# STM32F405GTV6.net
KiCad netlist of a schematic drawn in Altium Designer
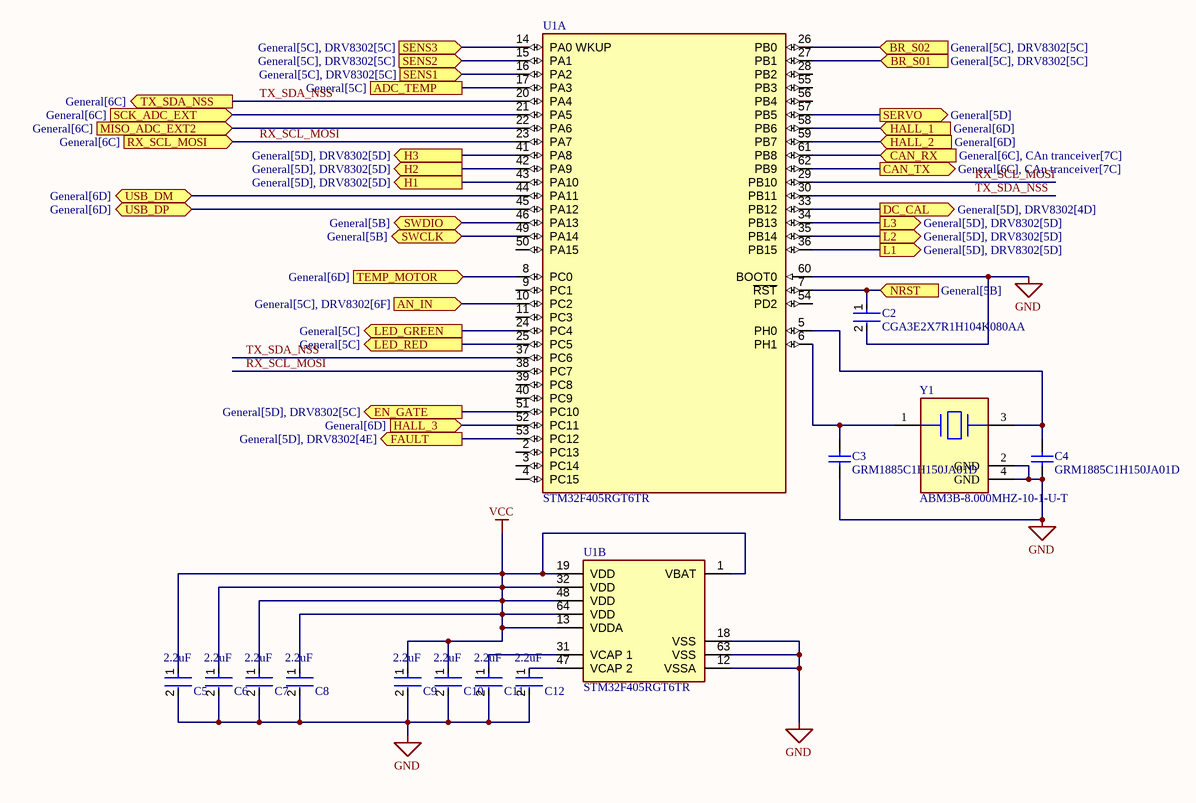
[diagram p0: STM32F405GTV6.SchDoc]

(export (version "E")
  (design (tool "Eeschema 10.0.6"))
  (components
    (comp (ref "C2")
      (value "CGA3E2X7R1H104K080AA")
      (footprint "FP-CGA3E-0_3-0_1-IPC_A")
      (description "Cap Ceramic 100nF 50V X7R 10% Pad SMD 0603 +125°C Automotive T/R")
      (fields (field (name "TOLERANCE") "10%") (field (name "VOLTAGE") "50V"))
      (libsource (lib "Altium Content Vault") (part "b4654b650e69147ec39a6b967a45e02"))
    )
    (comp (ref "C3")
      (value "GRM1885C1H150JA01D")
      (footprint "CAPC1608X90X35ML10T15")
      (fields (field (name "MANUFACTURER") "Murata"))
      (libsource (lib "Altium Content Vault") (part "CAP"))
    )
    (comp (ref "C4")
      (value "GRM1885C1H150JA01D")
      (footprint "CAPC1608X90X35ML10T15")
      (fields (field (name "MANUFACTURER") "Murata"))
      (libsource (lib "Altium Content Vault") (part "CAP"))
    )
    (comp (ref "C5")
      (value "GRM188R71A225KE15D")
      (footprint "FP-GRM188-0_1-e0_2_0_5-MFG")
      (description "Chip Multilayer Ceramic Capacitors for General Purpose, 0603, 2.2uF, X7R, 15%, 10%, 10V")
      (fields
        (field (name "VOLTAGE") "10V")
        (field (name "CAPACITANCE") "2.2uF")
        (field (name "TOLERANCE") "10%")
      )
      (libsource (lib "Altium Content Vault") (part "11868f565c42a9108669ba33697ecf6"))
    )
    (comp (ref "C6")
      (value "GRM188R71A225KE15D")
      (footprint "FP-GRM188-0_1-e0_2_0_5-MFG")
      (description "Chip Multilayer Ceramic Capacitors for General Purpose, 0603, 2.2uF, X7R, 15%, 10%, 10V")
      (fields
        (field (name "VOLTAGE") "10V")
        (field (name "CAPACITANCE") "2.2uF")
        (field (name "TOLERANCE") "10%")
      )
      (libsource (lib "Altium Content Vault") (part "11868f565c42a9108669ba33697ecf6"))
    )
    (comp (ref "C7")
      (value "GRM188R71A225KE15D")
      (footprint "FP-GRM188-0_1-e0_2_0_5-MFG")
      (description "Chip Multilayer Ceramic Capacitors for General Purpose, 0603, 2.2uF, X7R, 15%, 10%, 10V")
      (fields
        (field (name "VOLTAGE") "10V")
        (field (name "CAPACITANCE") "2.2uF")
        (field (name "TOLERANCE") "10%")
      )
      (libsource (lib "Altium Content Vault") (part "11868f565c42a9108669ba33697ecf6"))
    )
    (comp (ref "C8")
      (value "GRM188R71A225KE15D")
      (footprint "FP-GRM188-0_1-e0_2_0_5-MFG")
      (description "Chip Multilayer Ceramic Capacitors for General Purpose, 0603, 2.2uF, X7R, 15%, 10%, 10V")
      (fields
        (field (name "VOLTAGE") "10V")
        (field (name "CAPACITANCE") "2.2uF")
        (field (name "TOLERANCE") "10%")
      )
      (libsource (lib "Altium Content Vault") (part "11868f565c42a9108669ba33697ecf6"))
    )
    (comp (ref "C9")
      (value "GRM188R71A225KE15D")
      (footprint "FP-GRM188-0_1-e0_2_0_5-MFG")
      (description "Chip Multilayer Ceramic Capacitors for General Purpose, 0603, 2.2uF, X7R, 15%, 10%, 10V")
      (fields
        (field (name "VOLTAGE") "10V")
        (field (name "CAPACITANCE") "2.2uF")
        (field (name "TOLERANCE") "10%")
      )
      (libsource (lib "Altium Content Vault") (part "11868f565c42a9108669ba33697ecf6"))
    )
    (comp (ref "C10")
      (value "GRM188R71A225KE15D")
      (footprint "FP-GRM188-0_1-e0_2_0_5-MFG")
      (description "Chip Multilayer Ceramic Capacitors for General Purpose, 0603, 2.2uF, X7R, 15%, 10%, 10V")
      (fields
        (field (name "VOLTAGE") "10V")
        (field (name "CAPACITANCE") "2.2uF")
        (field (name "TOLERANCE") "10%")
      )
      (libsource (lib "Altium Content Vault") (part "11868f565c42a9108669ba33697ecf6"))
    )
    (comp (ref "C11")
      (value "GRM188R71A225KE15D")
      (footprint "FP-GRM188-0_1-e0_2_0_5-MFG")
      (description "Chip Multilayer Ceramic Capacitors for General Purpose, 0603, 2.2uF, X7R, 15%, 10%, 10V")
      (fields
        (field (name "VOLTAGE") "10V")
        (field (name "CAPACITANCE") "2.2uF")
        (field (name "TOLERANCE") "10%")
      )
      (libsource (lib "Altium Content Vault") (part "11868f565c42a9108669ba33697ecf6"))
    )
    (comp (ref "C12")
      (value "2u2")
      (footprint "FP-GRM188-0_1-e0_2_0_5-MFG")
      (description "Chip Multilayer Ceramic Capacitors for General Purpose, 0603, 2.2uF, X7R, 15%, 10%, 10V")
      (fields
        (field (name "VOLTAGE") "10V")
        (field (name "CAPACITANCE") "2.2uF")
        (field (name "TOLERANCE") "10%")
      )
      (libsource (lib "Altium Content Vault") (part "11868f565c42a9108669ba33697ecf6"))
    )
    (comp (ref "U1")
      (value "STM32F405RGT6TR")
      (footprint "FP-LQFP64-5W-IPC_C")
      (description "IC MCU 32BIT 1MB FLASH 64LQFP")
      (libsource (lib "Altium Content Vault") (part "179ee1be0515346e2f7079deece093b"))
    )
    (comp (ref "Y1")
      (value "ABM3B-8.000MHZ-10-1-U-T")
      (footprint "FP-ABM3B-MFG")
      (description "Crystal 8MHz ±10ppm 10pF SMD-4 5mm x 3.2mm")
      (libsource (lib "Altium Content Vault") (part "48e526d86b7f2615d98721063c72f49"))
    )
  )
  (nets
    (net (code "1") (name "/ADC_TEMP") (class "Default")
      (node (ref "U1") (pin "17") (pinfunction "PA3_17") (pintype "bidirectional"))
    )
    (net (code "2") (name "/AN_IN") (class "Default")
      (node (ref "U1") (pin "10") (pinfunction "PC2_10") (pintype "bidirectional"))
    )
    (net (code "3") (name "/BR_S01") (class "Default")
      (node (ref "U1") (pin "27") (pinfunction "PB1_27") (pintype "bidirectional"))
    )
    (net (code "4") (name "/BR_S02") (class "Default")
      (node (ref "U1") (pin "26") (pinfunction "PB0_26") (pintype "bidirectional"))
    )
    (net (code "5") (name "/CAN_RX") (class "Default")
      (node (ref "U1") (pin "61") (pinfunction "PB8_61") (pintype "bidirectional"))
    )
    (net (code "6") (name "/CAN_TX") (class "Default")
      (node (ref "U1") (pin "62") (pinfunction "PB9_62") (pintype "bidirectional"))
    )
    (net (code "7") (name "/DC_CAL") (class "Default")
      (node (ref "U1") (pin "33") (pinfunction "PB12_33") (pintype "bidirectional"))
    )
    (net (code "8") (name "/EN_GATE") (class "Default")
      (node (ref "U1") (pin "51") (pinfunction "PC10_51") (pintype "bidirectional"))
    )
    (net (code "9") (name "/FAULT") (class "Default")
      (node (ref "U1") (pin "53") (pinfunction "PC12_53") (pintype "bidirectional"))
    )
    (net (code "10") (name "/H1") (class "Default")
      (node (ref "U1") (pin "43") (pinfunction "PA10_43") (pintype "bidirectional"))
    )
    (net (code "11") (name "/H2") (class "Default")
      (node (ref "U1") (pin "42") (pinfunction "PA9_42") (pintype "bidirectional"))
    )
    (net (code "12") (name "/H3") (class "Default")
      (node (ref "U1") (pin "41") (pinfunction "PA8_41") (pintype "bidirectional"))
    )
    (net (code "13") (name "/HALL_1") (class "Default")
      (node (ref "U1") (pin "58") (pinfunction "PB6_58") (pintype "bidirectional"))
    )
    (net (code "14") (name "/HALL_2") (class "Default")
      (node (ref "U1") (pin "59") (pinfunction "PB7_59") (pintype "bidirectional"))
    )
    (net (code "15") (name "/HALL_3") (class "Default")
      (node (ref "U1") (pin "52") (pinfunction "PC11_52") (pintype "bidirectional"))
    )
    (net (code "16") (name "/L1") (class "Default")
      (node (ref "U1") (pin "36") (pinfunction "PB15_36") (pintype "bidirectional"))
    )
    (net (code "17") (name "/L2") (class "Default")
      (node (ref "U1") (pin "35") (pinfunction "PB14_35") (pintype "bidirectional"))
    )
    (net (code "18") (name "/L3") (class "Default")
      (node (ref "U1") (pin "34") (pinfunction "PB13_34") (pintype "bidirectional"))
    )
    (net (code "19") (name "/LED_GREEN") (class "Default")
      (node (ref "U1") (pin "24") (pinfunction "PC4_24") (pintype "bidirectional"))
    )
    (net (code "20") (name "/LED_RED") (class "Default")
      (node (ref "U1") (pin "25") (pinfunction "PC5_25") (pintype "bidirectional"))
    )
    (net (code "21") (name "/MISO_ADC_EXT2") (class "Default")
      (node (ref "U1") (pin "22") (pinfunction "PA6_22") (pintype "bidirectional"))
    )
    (net (code "22") (name "/NRST") (class "Default")
      (node (ref "C2") (pin "1") (pinfunction "1_1") (pintype "passive"))
      (node (ref "U1") (pin "7") (pinfunction "~{RST}_7") (pintype "bidirectional"))
    )
    (net (code "23") (name "/RX_SCL_MOSI") (class "Default")
      (node (ref "U1") (pin "23") (pinfunction "PA7_23") (pintype "bidirectional"))
      (node (ref "U1") (pin "29") (pinfunction "PB10_29") (pintype "bidirectional"))
      (node (ref "U1") (pin "38") (pinfunction "PC7_38") (pintype "bidirectional"))
    )
    (net (code "24") (name "/SCK_ADC_EXT") (class "Default")
      (node (ref "U1") (pin "21") (pinfunction "PA5_21") (pintype "bidirectional"))
    )
    (net (code "25") (name "/SENS1") (class "Default")
      (node (ref "U1") (pin "16") (pinfunction "PA2_16") (pintype "bidirectional"))
    )
    (net (code "26") (name "/SENS2") (class "Default")
      (node (ref "U1") (pin "15") (pinfunction "PA1_15") (pintype "bidirectional"))
    )
    (net (code "27") (name "/SENS3") (class "Default")
      (node (ref "U1") (pin "14") (pinfunction "PA0_WKUP_14") (pintype "bidirectional"))
    )
    (net (code "28") (name "/SERVO") (class "Default")
      (node (ref "U1") (pin "57") (pinfunction "PB5_57") (pintype "bidirectional"))
    )
    (net (code "29") (name "/SWCLK") (class "Default")
      (node (ref "U1") (pin "49") (pinfunction "PA14_49") (pintype "bidirectional"))
    )
    (net (code "30") (name "/SWDIO") (class "Default")
      (node (ref "U1") (pin "46") (pinfunction "PA13_46") (pintype "bidirectional"))
    )
    (net (code "31") (name "/TEMP_MOTOR") (class "Default")
      (node (ref "U1") (pin "8") (pinfunction "PC0_8") (pintype "bidirectional"))
    )
    (net (code "32") (name "/TX_SDA_NSS") (class "Default")
      (node (ref "U1") (pin "20") (pinfunction "PA4_20") (pintype "bidirectional"))
      (node (ref "U1") (pin "30") (pinfunction "PB11_30") (pintype "bidirectional"))
      (node (ref "U1") (pin "37") (pinfunction "PC6_37") (pintype "bidirectional"))
    )
    (net (code "33") (name "/USB_DM") (class "Default")
      (node (ref "U1") (pin "44") (pinfunction "PA11_44") (pintype "bidirectional"))
    )
    (net (code "34") (name "/USB_DP") (class "Default")
      (node (ref "U1") (pin "45") (pinfunction "PA12_45") (pintype "bidirectional"))
    )
    (net (code "35") (name "GND") (class "Default")
      (node (ref "C10") (pin "2") (pinfunction "2_2") (pintype "passive"))
      (node (ref "C11") (pin "2") (pinfunction "2_2") (pintype "passive"))
      (node (ref "C12") (pin "2") (pinfunction "2_2") (pintype "passive"))
      (node (ref "C2") (pin "2") (pinfunction "2_2") (pintype "passive"))
      (node (ref "C3") (pin "1") (pinfunction "1_1") (pintype "passive"))
      (node (ref "C4") (pin "1") (pinfunction "1_1") (pintype "passive"))
      (node (ref "C5") (pin "2") (pinfunction "2_2") (pintype "passive"))
      (node (ref "C6") (pin "2") (pinfunction "2_2") (pintype "passive"))
      (node (ref "C7") (pin "2") (pinfunction "2_2") (pintype "passive"))
      (node (ref "C8") (pin "2") (pinfunction "2_2") (pintype "passive"))
      (node (ref "C9") (pin "2") (pinfunction "2_2") (pintype "passive"))
      (node (ref "U1") (pin "12") (pinfunction "VSSA_12") (pintype "power_in"))
      (node (ref "U1") (pin "18") (pinfunction "VSS_18") (pintype "power_in"))
      (node (ref "U1") (pin "60") (pinfunction "BOOT0_60") (pintype "input"))
      (node (ref "U1") (pin "63") (pinfunction "VSS_63") (pintype "power_in"))
      (node (ref "Y1") (pin "2") (pinfunction "GND_2") (pintype "power_in"))
      (node (ref "Y1") (pin "4") (pinfunction "GND_4") (pintype "power_in"))
    )
    (net (code "36") (name "Net-(U1A-PH0)") (class "Default")
      (node (ref "C4") (pin "2") (pinfunction "2_2") (pintype "passive"))
      (node (ref "U1") (pin "5") (pinfunction "PH0_5") (pintype "bidirectional"))
      (node (ref "Y1") (pin "3") (pinfunction "3_3") (pintype "passive"))
    )
    (net (code "37") (name "Net-(U1A-PH1)") (class "Default")
      (node (ref "C3") (pin "2") (pinfunction "2_2") (pintype "passive"))
      (node (ref "U1") (pin "6") (pinfunction "PH1_6") (pintype "bidirectional"))
      (node (ref "Y1") (pin "1") (pinfunction "1_1") (pintype "passive"))
    )
    (net (code "38") (name "Net-(U1B-VCAP_1)") (class "Default")
      (node (ref "C11") (pin "1") (pinfunction "1_1") (pintype "passive"))
      (node (ref "U1") (pin "31") (pinfunction "VCAP_1_31") (pintype "passive"))
    )
    (net (code "39") (name "Net-(U1B-VCAP_2)") (class "Default")
      (node (ref "C12") (pin "1") (pinfunction "1_1") (pintype "passive"))
      (node (ref "U1") (pin "47") (pinfunction "VCAP_2_47") (pintype "passive"))
    )
    (net (code "40") (name "VCC") (class "Default")
      (node (ref "C10") (pin "1") (pinfunction "1_1") (pintype "passive"))
      (node (ref "C5") (pin "1") (pinfunction "1_1") (pintype "passive"))
      (node (ref "C6") (pin "1") (pinfunction "1_1") (pintype "passive"))
      (node (ref "C7") (pin "1") (pinfunction "1_1") (pintype "passive"))
      (node (ref "C8") (pin "1") (pinfunction "1_1") (pintype "passive"))
      (node (ref "C9") (pin "1") (pinfunction "1_1") (pintype "passive"))
      (node (ref "U1") (pin "1") (pinfunction "VBAT_1") (pintype "power_in"))
      (node (ref "U1") (pin "13") (pinfunction "VDDA_13") (pintype "power_in"))
      (node (ref "U1") (pin "19") (pinfunction "VDD_19") (pintype "power_in"))
      (node (ref "U1") (pin "32") (pinfunction "VDD_32") (pintype "power_in"))
      (node (ref "U1") (pin "48") (pinfunction "VDD_48") (pintype "power_in"))
      (node (ref "U1") (pin "64") (pinfunction "VDD_64") (pintype "power_in"))
    )
    (net (code "41") (name "unconnected-(U1A-PA15-Pad50)") (class "Default")
      (node (ref "U1") (pin "50") (pinfunction "PA15_50") (pintype "bidirectional"))
    )
    (net (code "42") (name "unconnected-(U1A-PB2-Pad28)") (class "Default")
      (node (ref "U1") (pin "28") (pinfunction "PB2_28") (pintype "bidirectional"))
    )
    (net (code "43") (name "unconnected-(U1A-PB3-Pad55)") (class "Default")
      (node (ref "U1") (pin "55") (pinfunction "PB3_55") (pintype "bidirectional"))
    )
    (net (code "44") (name "unconnected-(U1A-PB4-Pad56)") (class "Default")
      (node (ref "U1") (pin "56") (pinfunction "PB4_56") (pintype "bidirectional"))
    )
    (net (code "45") (name "unconnected-(U1A-PC1-Pad9)") (class "Default")
      (node (ref "U1") (pin "9") (pinfunction "PC1_9") (pintype "bidirectional"))
    )
    (net (code "46") (name "unconnected-(U1A-PC3-Pad11)") (class "Default")
      (node (ref "U1") (pin "11") (pinfunction "PC3_11") (pintype "bidirectional"))
    )
    (net (code "47") (name "unconnected-(U1A-PC8-Pad39)") (class "Default")
      (node (ref "U1") (pin "39") (pinfunction "PC8_39") (pintype "bidirectional"))
    )
    (net (code "48") (name "unconnected-(U1A-PC9-Pad40)") (class "Default")
      (node (ref "U1") (pin "40") (pinfunction "PC9_40") (pintype "bidirectional"))
    )
    (net (code "49") (name "unconnected-(U1A-PC13-Pad2)") (class "Default")
      (node (ref "U1") (pin "2") (pinfunction "PC13_2") (pintype "bidirectional"))
    )
    (net (code "50") (name "unconnected-(U1A-PC14-Pad3)") (class "Default")
      (node (ref "U1") (pin "3") (pinfunction "PC14_3") (pintype "bidirectional"))
    )
    (net (code "51") (name "unconnected-(U1A-PC15-Pad4)") (class "Default")
      (node (ref "U1") (pin "4") (pinfunction "PC15_4") (pintype "bidirectional"))
    )
    (net (code "52") (name "unconnected-(U1A-PD2-Pad54)") (class "Default")
      (node (ref "U1") (pin "54") (pinfunction "PD2_54") (pintype "bidirectional"))
    )
  )
)
